# spi_flash.net
KiCad netlist of a schematic drawn in Altium Designer
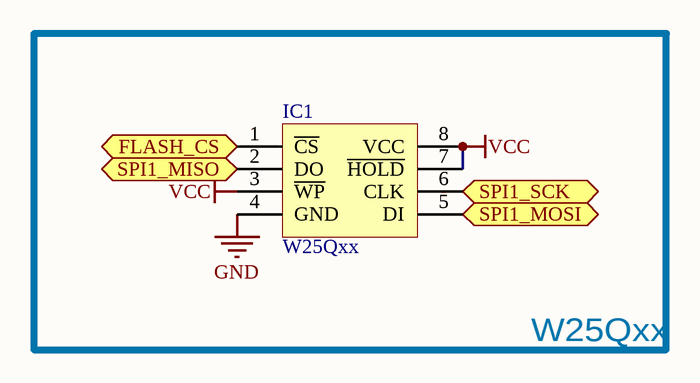
[diagram p0: spi_flash.SchDoc]

(export (version "E")
  (design (tool "Eeschema 10.0.6"))
  (components
    (comp (ref "IC1")
      (value "W25Qxx")
      (footprint "SOP8W_N")
      (description "外置Flash")
      (fields (field (name "版权归属") "源创客"))
      (libsource (lib "1.1   - IC芯片") (part "W25Qxx"))
    )
  )
  (nets
    (net (code "1") (name "/FLASH_CS") (class "Default")
      (node (ref "IC1") (pin "1") (pinfunction "~{CS}_1") (pintype "passive"))
    )
    (net (code "2") (name "/SPI1_MISO") (class "Default")
      (node (ref "IC1") (pin "2") (pinfunction "DO_2") (pintype "passive"))
    )
    (net (code "3") (name "/SPI1_MOSI") (class "Default")
      (node (ref "IC1") (pin "5") (pinfunction "DI_5") (pintype "passive"))
    )
    (net (code "4") (name "/SPI1_SCK") (class "Default")
      (node (ref "IC1") (pin "6") (pinfunction "CLK_6") (pintype "passive"))
    )
    (net (code "5") (name "GND") (class "Default")
      (node (ref "IC1") (pin "4") (pinfunction "GND_4") (pintype "passive"))
    )
    (net (code "6") (name "VCC") (class "Default")
      (node (ref "IC1") (pin "3") (pinfunction "~{WP}_3") (pintype "passive"))
      (node (ref "IC1") (pin "7") (pinfunction "~{HOLD}_7") (pintype "passive"))
      (node (ref "IC1") (pin "8") (pinfunction "VCC_8") (pintype "passive"))
    )
  )
)
